# CP2102.net
KiCad netlist of a schematic drawn in Altium Designer
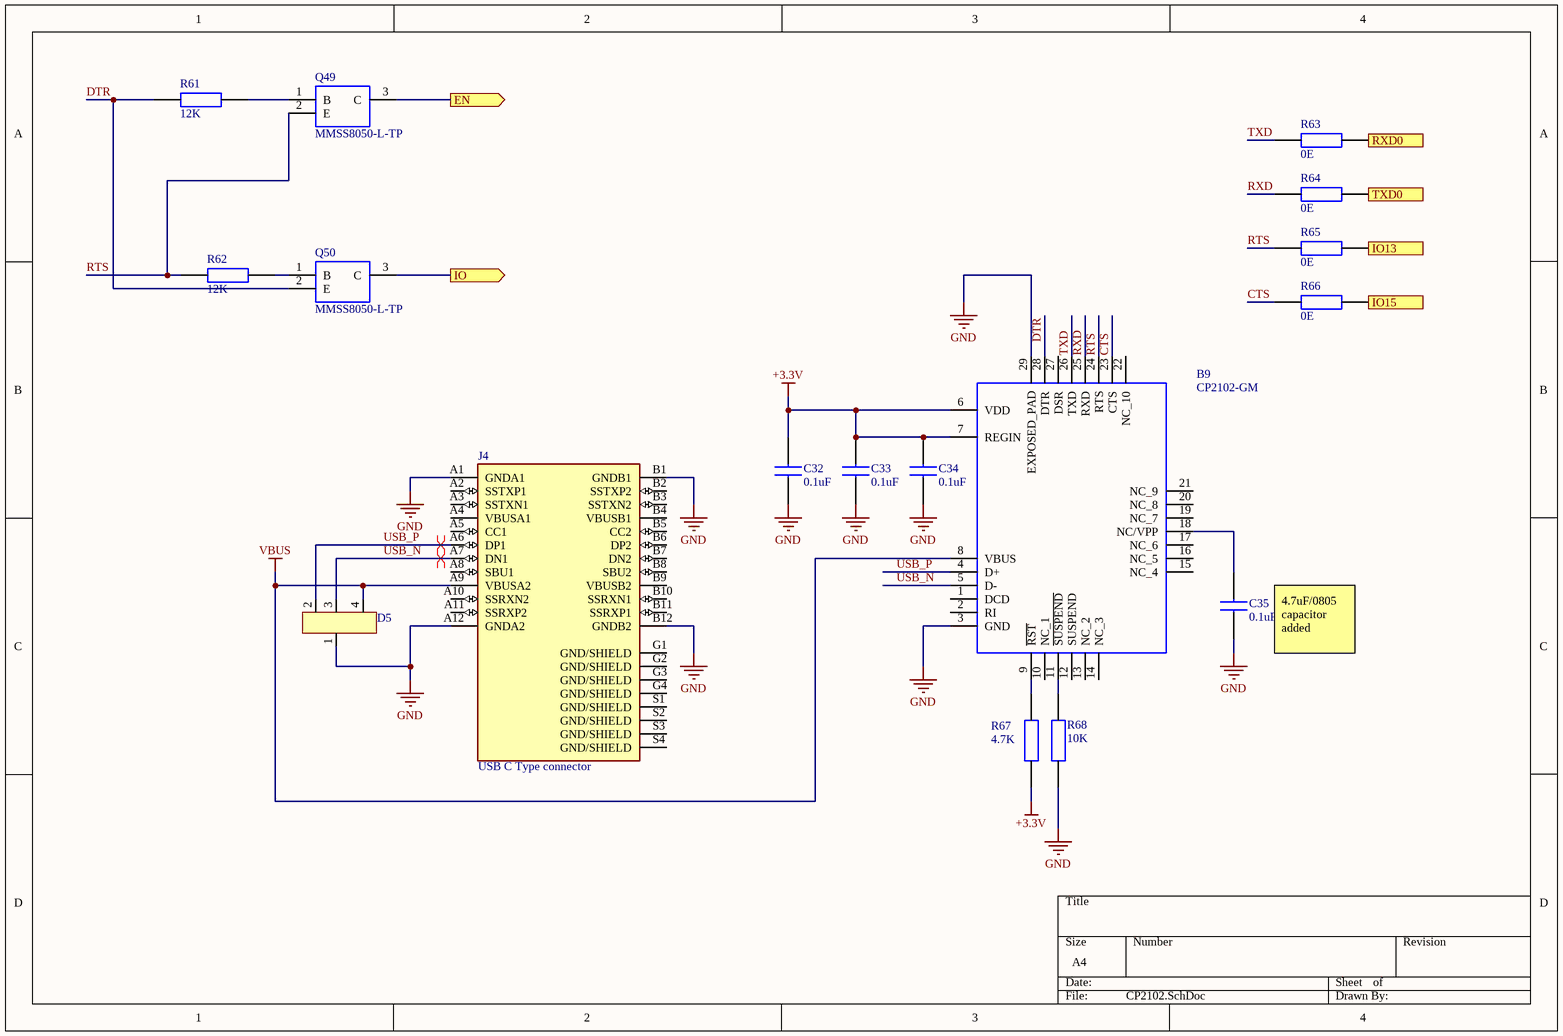
[diagram p0: CP2102.SchDoc]

(export (version "E")
  (design (tool "Eeschema 10.0.6"))
  (components
    (comp (ref "B9")
      (value "CP2102-GM")
      (footprint "QFN-28")
      (description "CP2102-GM, USB Controller 12Mbit/s USB 2.0, 3.3 V, 28-Pin, QFN")
      (fields (field (name "MOUSER PART NUMBER") "634-CP2102-GM"))
      (libsource (lib "CV-R-BAP_V2.1.5") (part "CP2102-GM"))
    )
    (comp (ref "C32")
      (value "0.1uF")
      (footprint "CAPC1005X55N")
      (description "Multilayer Ceramic Capacitors MLCC - SMD/SMT 16V 0.1uF X7R 0402 20%")
      (fields (field (name "MANUFACTURER") "Kemet") (field (name "PART NUMBER") "C0402C104M4RECTU"))
      (libsource (lib "CV-RT-BAP_v2.1.4") (part "C0402C104M4RECTU"))
    )
    (comp (ref "C33")
      (value "0.1uF")
      (footprint "CAPC1005X55N")
      (description "Multilayer Ceramic Capacitors MLCC - SMD/SMT 16V 0.1uF X7R 0402 20%")
      (fields (field (name "MANUFACTURER") "Kemet") (field (name "PART NUMBER") "C0402C104M4RECTU"))
      (libsource (lib "CV-RT-BAP_v2.1.4") (part "C0402C104M4RECTU"))
    )
    (comp (ref "C34")
      (value "0.1uF")
      (footprint "CAPC1005X55N")
      (description "Multilayer Ceramic Capacitors MLCC - SMD/SMT 16V 0.1uF X7R 0402 20%")
      (fields (field (name "MANUFACTURER") "Kemet") (field (name "PART NUMBER") "C0402C104M4RECTU"))
      (libsource (lib "CV-RT-BAP_v2.1.4") (part "C0402C104M4RECTU"))
    )
    (comp (ref "C35")
      (value "0.1uF")
      (footprint "CAPC1005X55N")
      (description "Multilayer Ceramic Capacitors MLCC - SMD/SMT 16V 0.1uF X7R 0402 20%")
      (fields (field (name "MANUFACTURER") "Kemet") (field (name "PART NUMBER") "C0402C104M4RECTU"))
      (libsource (lib "CV-RT-BAP_v2.1.4") (part "C0402C104M4RECTU"))
    )
    (comp (ref "D5")
      (value "SP0504BAJTG_ESD Diode")
      (footprint "SOT-143-4")
      (fields (field (name "PART NUMBER") "SP0503BAHTG") (field (name "MANUFACTURER") "Little Fuse"))
      (libsource (lib "CV-R-BAP_V2.1.5") (part "SP0504BAJTG_ESD Diode"))
    )
    (comp (ref "J4")
      (value "USB C Type connector")
      (footprint "USB C Type connector")
      (fields (field (name "PART NUMBER") "632723100011"))
      (libsource (lib "CV-R-BAP_V2.1.5") (part "USB C Type connector"))
    )
    (comp (ref "Q49")
      (value "MMSS8050-L-TP")
      (footprint "SOT96P237X112-3N")
      (description "Bipolar Transistors - BJT 625mW, 25V, 1500mA")
      (fields (field (name "MOUSER PART NUMBER") "833-MMSS8050-L-TP"))
      (libsource (lib "S8050") (part "MMSS8050-L-TP"))
    )
    (comp (ref "Q50")
      (value "MMSS8050-L-TP")
      (footprint "SOT96P237X112-3N")
      (description "Bipolar Transistors - BJT 625mW, 25V, 1500mA")
      (fields (field (name "MOUSER PART NUMBER") "833-MMSS8050-L-TP"))
      (libsource (lib "S8050") (part "MMSS8050-L-TP"))
    )
    (comp (ref "R61")
      (value "12K")
      (footprint "RESC1005X40N")
      (description "RESISTOR, 0402 12K Ohms +/-1% 1/16 W")
      (fields
        (field (name "MANUFACTURER_PART_NUMBER") "RC0402FR-0712KL")
        (field (name "MOUSER PART NUMBER") "603-RC0402FR-0712KL")
      )
      (libsource (lib "12K_0402") (part "RC0402FR-0712KL"))
    )
    (comp (ref "R62")
      (value "12K")
      (footprint "RESC1005X40N")
      (description "RESISTOR, 0402 12K Ohms +/-1% 1/16 W")
      (fields
        (field (name "MANUFACTURER_PART_NUMBER") "RC0402FR-0712KL")
        (field (name "MOUSER PART NUMBER") "603-RC0402FR-0712KL")
      )
      (libsource (lib "12K_0402") (part "RC0402FR-0712KL"))
    )
    (comp (ref "R63")
      (value "0E")
      (footprint "RESC1005X40N")
      (description "Thick Film Resistors - SMD 0.0ohm 1%")
      (fields
        (field (name "MANUFACTURER_PART_NUMBER") "RC0402FR-070RL")
        (field (name "MOUSER PART NUMBER") "603-RC0402FR-070RL")
      )
      (libsource (lib "0E_0402") (part "RC0402FR-070RL"))
    )
    (comp (ref "R64")
      (value "0E")
      (footprint "RESC1005X40N")
      (description "Thick Film Resistors - SMD 0.0ohm 1%")
      (fields
        (field (name "MANUFACTURER_PART_NUMBER") "RC0402FR-070RL")
        (field (name "MOUSER PART NUMBER") "603-RC0402FR-070RL")
      )
      (libsource (lib "0E_0402") (part "RC0402FR-070RL"))
    )
    (comp (ref "R65")
      (value "0E")
      (footprint "RESC1005X40N")
      (description "Thick Film Resistors - SMD 0.0ohm 1%")
      (fields
        (field (name "MANUFACTURER_PART_NUMBER") "RC0402FR-070RL")
        (field (name "MOUSER PART NUMBER") "603-RC0402FR-070RL")
      )
      (libsource (lib "0E_0402") (part "RC0402FR-070RL"))
    )
    (comp (ref "R66")
      (value "0E")
      (footprint "RESC1005X40N")
      (description "Thick Film Resistors - SMD 0.0ohm 1%")
      (fields
        (field (name "MANUFACTURER_PART_NUMBER") "RC0402FR-070RL")
        (field (name "MOUSER PART NUMBER") "603-RC0402FR-070RL")
      )
      (libsource (lib "0E_0402") (part "RC0402FR-070RL"))
    )
    (comp (ref "R67")
      (value "4.7K")
      (footprint "RESC1005X40N")
      (description "YAGEO (PHYCOMP) - RC0402FR-074K7L - RES, THICK FILM, 4K7, 1%, 0.063W, 0402")
      (fields
        (field (name "MANUFACTURER_PART_NUMBER") "RC0402FR-074K7L")
        (field (name "MOUSER PART NUMBER") "603-RC0402FR-074K7L")
      )
      (libsource (lib "4.7K_0402") (part "RC0402FR-074K7L"))
    )
    (comp (ref "R68")
      (value "10K")
      (footprint "RESC1005X40N")
      (description "YAGEO (PHYCOMP) - RC0402JR-0710KL - RES, THICK FILM, 10K, 5%, 0.0625W, 0402")
      (fields
        (field (name "MANUFACTURER_PART_NUMBER") "RC0402JR-0710KL")
        (field (name "MOUSER PART NUMBER") "603-RC0402JR-0710KL")
      )
      (libsource (lib "10K_0402") (part "RC0402JR-0710KL"))
    )
  )
  (nets
    (net (code "1") (name "+3.3V") (class "Default")
      (node (ref "B9") (pin "6") (pinfunction "VDD_6") (pintype "power_in"))
      (node (ref "B9") (pin "7") (pinfunction "REGIN_7") (pintype "passive"))
      (node (ref "C32") (pin "2") (pinfunction "2_2") (pintype "passive"))
      (node (ref "C33") (pin "2") (pinfunction "2_2") (pintype "passive"))
      (node (ref "C34") (pin "2") (pinfunction "2_2") (pintype "passive"))
      (node (ref "R67") (pin "1") (pinfunction "1_1") (pintype "passive"))
    )
    (net (code "2") (name "/CTS") (class "Default")
      (node (ref "B9") (pin "23") (pinfunction "CTS_23") (pintype "passive"))
      (node (ref "R66") (pin "1") (pinfunction "1_1") (pintype "passive"))
    )
    (net (code "3") (name "/DTR") (class "Default")
      (node (ref "B9") (pin "28") (pinfunction "DTR_28") (pintype "passive"))
      (node (ref "Q50") (pin "2") (pinfunction "E_2") (pintype "passive"))
      (node (ref "R61") (pin "1") (pinfunction "1_1") (pintype "passive"))
    )
    (net (code "4") (name "/EN") (class "Default")
      (node (ref "Q49") (pin "3") (pinfunction "C_3") (pintype "passive"))
    )
    (net (code "5") (name "/IO") (class "Default")
      (node (ref "Q50") (pin "3") (pinfunction "C_3") (pintype "passive"))
    )
    (net (code "6") (name "/IO13") (class "Default")
      (node (ref "R65") (pin "2") (pinfunction "2_2") (pintype "passive"))
    )
    (net (code "7") (name "/IO15") (class "Default")
      (node (ref "R66") (pin "2") (pinfunction "2_2") (pintype "passive"))
    )
    (net (code "8") (name "/RTS") (class "Default")
      (node (ref "B9") (pin "24") (pinfunction "RTS_24") (pintype "passive"))
      (node (ref "Q49") (pin "2") (pinfunction "E_2") (pintype "passive"))
      (node (ref "R62") (pin "1") (pinfunction "1_1") (pintype "passive"))
      (node (ref "R65") (pin "1") (pinfunction "1_1") (pintype "passive"))
    )
    (net (code "9") (name "/RXD") (class "Default")
      (node (ref "B9") (pin "25") (pinfunction "RXD_25") (pintype "passive"))
      (node (ref "R64") (pin "1") (pinfunction "1_1") (pintype "passive"))
    )
    (net (code "10") (name "/RXD0") (class "Default")
      (node (ref "R63") (pin "2") (pinfunction "2_2") (pintype "passive"))
    )
    (net (code "11") (name "/TXD") (class "Default")
      (node (ref "B9") (pin "26") (pinfunction "TXD_26") (pintype "passive"))
      (node (ref "R63") (pin "1") (pinfunction "1_1") (pintype "passive"))
    )
    (net (code "12") (name "/TXD0") (class "Default")
      (node (ref "R64") (pin "2") (pinfunction "2_2") (pintype "passive"))
    )
    (net (code "13") (name "/USB_N") (class "Default")
      (node (ref "B9") (pin "5") (pinfunction "D-_5") (pintype "passive"))
      (node (ref "D5") (pin "3") (pinfunction "3_3") (pintype "passive"))
      (node (ref "J4") (pin "A7") (pinfunction "DN1_A7") (pintype "bidirectional"))
    )
    (net (code "14") (name "/USB_P") (class "Default")
      (node (ref "B9") (pin "4") (pinfunction "D+_4") (pintype "passive"))
      (node (ref "D5") (pin "2") (pinfunction "2_2") (pintype "passive"))
      (node (ref "J4") (pin "A6") (pinfunction "DP1_A6") (pintype "bidirectional"))
    )
    (net (code "15") (name "GND") (class "Default")
      (node (ref "B9") (pin "29") (pinfunction "EXPOSED_PAD_29") (pintype "passive"))
      (node (ref "B9") (pin "3") (pinfunction "GND_3") (pintype "passive"))
      (node (ref "C32") (pin "1") (pinfunction "1_1") (pintype "passive"))
      (node (ref "C33") (pin "1") (pinfunction "1_1") (pintype "passive"))
      (node (ref "C34") (pin "1") (pinfunction "1_1") (pintype "passive"))
      (node (ref "C35") (pin "1") (pinfunction "1_1") (pintype "passive"))
      (node (ref "D5") (pin "1") (pinfunction "1_1") (pintype "passive"))
      (node (ref "J4") (pin "A1") (pinfunction "GNDA1_A1") (pintype "power_in"))
      (node (ref "J4") (pin "A12") (pinfunction "GNDA2_A12") (pintype "power_in"))
      (node (ref "J4") (pin "B1") (pinfunction "GNDB1_B1") (pintype "power_in"))
      (node (ref "J4") (pin "B12") (pinfunction "GNDB2_B12") (pintype "power_in"))
      (node (ref "R68") (pin "1") (pinfunction "1_1") (pintype "passive"))
    )
    (net (code "16") (name "Net-(B9-NC{slash}VPP)") (class "Default")
      (node (ref "B9") (pin "18") (pinfunction "NC/VPP_18") (pintype "passive"))
      (node (ref "C35") (pin "2") (pinfunction "2_2") (pintype "passive"))
    )
    (net (code "17") (name "Net-(B9-RST)") (class "Default")
      (node (ref "B9") (pin "9") (pinfunction "RST_9") (pintype "passive"))
      (node (ref "R67") (pin "2") (pinfunction "2_2") (pintype "passive"))
    )
    (net (code "18") (name "Net-(B9-SUSPEND-Pad11)") (class "Default")
      (node (ref "B9") (pin "11") (pinfunction "SUSPEND_11") (pintype "passive"))
      (node (ref "R68") (pin "2") (pinfunction "2_2") (pintype "passive"))
    )
    (net (code "19") (name "Net-(Q49-B)") (class "Default")
      (node (ref "Q49") (pin "1") (pinfunction "B_1") (pintype "passive"))
      (node (ref "R61") (pin "2") (pinfunction "2_2") (pintype "passive"))
    )
    (net (code "20") (name "Net-(Q50-B)") (class "Default")
      (node (ref "Q50") (pin "1") (pinfunction "B_1") (pintype "passive"))
      (node (ref "R62") (pin "2") (pinfunction "2_2") (pintype "passive"))
    )
    (net (code "21") (name "VBUS") (class "Default")
      (node (ref "B9") (pin "8") (pinfunction "VBUS_8") (pintype "passive"))
      (node (ref "D5") (pin "4") (pinfunction "4_4") (pintype "passive"))
      (node (ref "J4") (pin "A9") (pinfunction "VBUSA2_A9") (pintype "power_in"))
    )
    (net (code "22") (name "unconnected-(B9-DCD-Pad1)") (class "Default")
      (node (ref "B9") (pin "1") (pinfunction "DCD_1") (pintype "passive"))
    )
    (net (code "23") (name "unconnected-(B9-DSR-Pad27)") (class "Default")
      (node (ref "B9") (pin "27") (pinfunction "DSR_27") (pintype "passive"))
    )
    (net (code "24") (name "unconnected-(B9-NC_1-Pad10)") (class "Default")
      (node (ref "B9") (pin "10") (pinfunction "NC_1_10") (pintype "passive"))
    )
    (net (code "25") (name "unconnected-(B9-NC_2-Pad13)") (class "Default")
      (node (ref "B9") (pin "13") (pinfunction "NC_2_13") (pintype "passive"))
    )
    (net (code "26") (name "unconnected-(B9-NC_3-Pad14)") (class "Default")
      (node (ref "B9") (pin "14") (pinfunction "NC_3_14") (pintype "passive"))
    )
    (net (code "27") (name "unconnected-(B9-NC_4-Pad15)") (class "Default")
      (node (ref "B9") (pin "15") (pinfunction "NC_4_15") (pintype "passive"))
    )
    (net (code "28") (name "unconnected-(B9-NC_5-Pad16)") (class "Default")
      (node (ref "B9") (pin "16") (pinfunction "NC_5_16") (pintype "passive"))
    )
    (net (code "29") (name "unconnected-(B9-NC_6-Pad17)") (class "Default")
      (node (ref "B9") (pin "17") (pinfunction "NC_6_17") (pintype "passive"))
    )
    (net (code "30") (name "unconnected-(B9-NC_7-Pad19)") (class "Default")
      (node (ref "B9") (pin "19") (pinfunction "NC_7_19") (pintype "passive"))
    )
    (net (code "31") (name "unconnected-(B9-NC_8-Pad20)") (class "Default")
      (node (ref "B9") (pin "20") (pinfunction "NC_8_20") (pintype "passive"))
    )
    (net (code "32") (name "unconnected-(B9-NC_9-Pad21)") (class "Default")
      (node (ref "B9") (pin "21") (pinfunction "NC_9_21") (pintype "passive"))
    )
    (net (code "33") (name "unconnected-(B9-NC_10-Pad22)") (class "Default")
      (node (ref "B9") (pin "22") (pinfunction "NC_10_22") (pintype "passive"))
    )
    (net (code "34") (name "unconnected-(B9-RI-Pad2)") (class "Default")
      (node (ref "B9") (pin "2") (pinfunction "RI_2") (pintype "passive"))
    )
    (net (code "35") (name "unconnected-(B9-SUSPEND-Pad12)") (class "Default")
      (node (ref "B9") (pin "12") (pinfunction "SUSPEND_12") (pintype "passive"))
    )
    (net (code "36") (name "unconnected-(J4-CC1-PadA5)") (class "Default")
      (node (ref "J4") (pin "A5") (pinfunction "CC1_A5") (pintype "bidirectional"))
    )
    (net (code "37") (name "unconnected-(J4-CC2-PadB5)") (class "Default")
      (node (ref "J4") (pin "B5") (pinfunction "CC2_B5") (pintype "bidirectional"))
    )
    (net (code "38") (name "unconnected-(J4-DN2-PadB7)") (class "Default")
      (node (ref "J4") (pin "B7") (pinfunction "DN2_B7") (pintype "bidirectional"))
    )
    (net (code "39") (name "unconnected-(J4-DP2-PadB6)") (class "Default")
      (node (ref "J4") (pin "B6") (pinfunction "DP2_B6") (pintype "bidirectional"))
    )
    (net (code "40") (name "unconnected-(J4-GND{slash}SHIELD-PadG1)") (class "Default")
      (node (ref "J4") (pin "G1") (pinfunction "GND/SHIELD_G1") (pintype "power_in"))
    )
    (net (code "41") (name "unconnected-(J4-GND{slash}SHIELD-PadG2)") (class "Default")
      (node (ref "J4") (pin "G2") (pinfunction "GND/SHIELD_G2") (pintype "power_in"))
    )
    (net (code "42") (name "unconnected-(J4-GND{slash}SHIELD-PadG3)") (class "Default")
      (node (ref "J4") (pin "G3") (pinfunction "GND/SHIELD_G3") (pintype "power_in"))
    )
    (net (code "43") (name "unconnected-(J4-GND{slash}SHIELD-PadG4)") (class "Default")
      (node (ref "J4") (pin "G4") (pinfunction "GND/SHIELD_G4") (pintype "power_in"))
    )
    (net (code "44") (name "unconnected-(J4-GND{slash}SHIELD-PadS1)") (class "Default")
      (node (ref "J4") (pin "S1") (pinfunction "GND/SHIELD_S1") (pintype "power_in"))
    )
    (net (code "45") (name "unconnected-(J4-GND{slash}SHIELD-PadS2)") (class "Default")
      (node (ref "J4") (pin "S2") (pinfunction "GND/SHIELD_S2") (pintype "power_in"))
    )
    (net (code "46") (name "unconnected-(J4-GND{slash}SHIELD-PadS3)") (class "Default")
      (node (ref "J4") (pin "S3") (pinfunction "GND/SHIELD_S3") (pintype "power_in"))
    )
    (net (code "47") (name "unconnected-(J4-GND{slash}SHIELD-PadS4)") (class "Default")
      (node (ref "J4") (pin "S4") (pinfunction "GND/SHIELD_S4") (pintype "power_in"))
    )
    (net (code "48") (name "unconnected-(J4-SBU1-PadA8)") (class "Default")
      (node (ref "J4") (pin "A8") (pinfunction "SBU1_A8") (pintype "bidirectional"))
    )
    (net (code "49") (name "unconnected-(J4-SBU2-PadB8)") (class "Default")
      (node (ref "J4") (pin "B8") (pinfunction "SBU2_B8") (pintype "bidirectional"))
    )
    (net (code "50") (name "unconnected-(J4-SSRXN1-PadB10)") (class "Default")
      (node (ref "J4") (pin "B10") (pinfunction "SSRXN1_B10") (pintype "bidirectional"))
    )
    (net (code "51") (name "unconnected-(J4-SSRXN2-PadA10)") (class "Default")
      (node (ref "J4") (pin "A10") (pinfunction "SSRXN2_A10") (pintype "bidirectional"))
    )
    (net (code "52") (name "unconnected-(J4-SSRXP1-PadB11)") (class "Default")
      (node (ref "J4") (pin "B11") (pinfunction "SSRXP1_B11") (pintype "bidirectional"))
    )
    (net (code "53") (name "unconnected-(J4-SSRXP2-PadA11)") (class "Default")
      (node (ref "J4") (pin "A11") (pinfunction "SSRXP2_A11") (pintype "bidirectional"))
    )
    (net (code "54") (name "unconnected-(J4-SSTXN1-PadA3)") (class "Default")
      (node (ref "J4") (pin "A3") (pinfunction "SSTXN1_A3") (pintype "bidirectional"))
    )
    (net (code "55") (name "unconnected-(J4-SSTXN2-PadB3)") (class "Default")
      (node (ref "J4") (pin "B3") (pinfunction "SSTXN2_B3") (pintype "bidirectional"))
    )
    (net (code "56") (name "unconnected-(J4-SSTXP1-PadA2)") (class "Default")
      (node (ref "J4") (pin "A2") (pinfunction "SSTXP1_A2") (pintype "bidirectional"))
    )
    (net (code "57") (name "unconnected-(J4-SSTXP2-PadB2)") (class "Default")
      (node (ref "J4") (pin "B2") (pinfunction "SSTXP2_B2") (pintype "bidirectional"))
    )
    (net (code "58") (name "unconnected-(J4-VBUSA1-PadA4)") (class "Default")
      (node (ref "J4") (pin "A4") (pinfunction "VBUSA1_A4") (pintype "power_in"))
    )
    (net (code "59") (name "unconnected-(J4-VBUSB1-PadB4)") (class "Default")
      (node (ref "J4") (pin "B4") (pinfunction "VBUSB1_B4") (pintype "power_in"))
    )
    (net (code "60") (name "unconnected-(J4-VBUSB2-PadB9)") (class "Default")
      (node (ref "J4") (pin "B9") (pinfunction "VBUSB2_B9") (pintype "power_in"))
    )
  )
)
